# driver-phase.net
KiCad netlist of a schematic drawn in Altium Designer
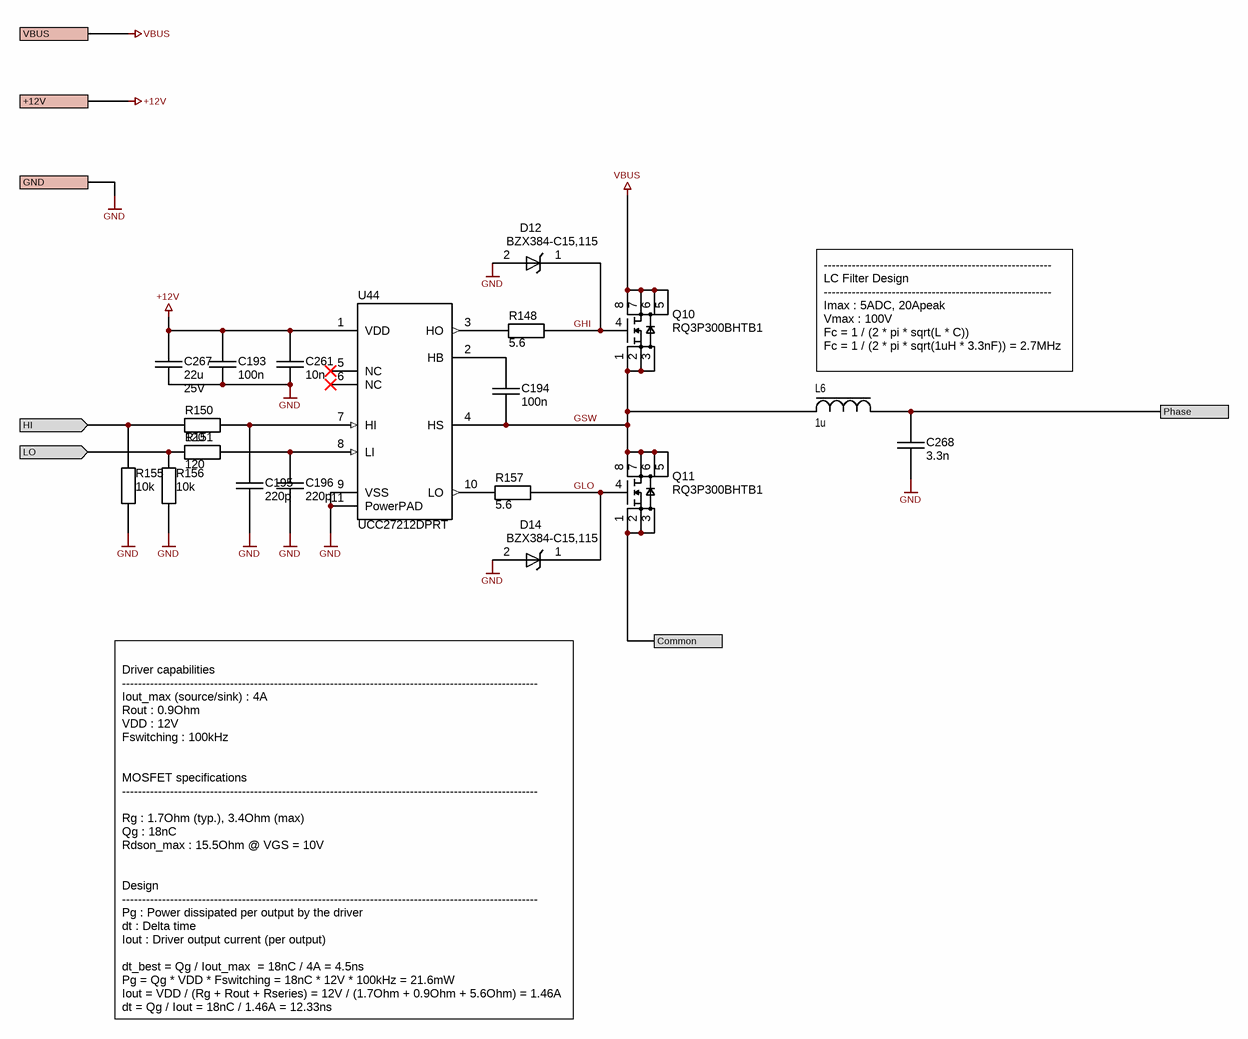
[diagram p0: driver-phase.SchDoc]

(export (version "E")
  (design (tool "Eeschema 10.0.6"))
  (components
    (comp (ref "C193")
      (value "100n")
      (footprint "SM/C0402")
      (description "100 nF ±10% 25V Ceramic Capacitor X5R 0402 (1005 Metric)")
      (fields (field (name "VOLTAGE") "25V"))
      (libsource (lib "motionboard") (part "CAP CER 100NF 25V X5R 0402"))
    )
    (comp (ref "C194")
      (value "100n")
      (footprint "SM/C0402")
      (description "100 nF ±10% 25V Ceramic Capacitor X5R 0402 (1005 Metric)")
      (fields (field (name "VOLTAGE") "25V"))
      (libsource (lib "motionboard") (part "CAP CER 100NF 25V X5R 0402"))
    )
    (comp (ref "C195")
      (value "220p")
      (footprint "SM/C0402")
      (description "220 pF ±5% 50V Ceramic Capacitor C0G, NP0 0402 (1005 Metric)")
      (fields (field (name "VOLTAGE") "50V"))
      (libsource (lib "motionboard") (part "CAP CER 220PF 50V C0G/NP0 0402"))
    )
    (comp (ref "C196")
      (value "220p")
      (footprint "SM/C0402")
      (description "220 pF ±5% 50V Ceramic Capacitor C0G, NP0 0402 (1005 Metric)")
      (fields (field (name "VOLTAGE") "50V"))
      (libsource (lib "motionboard") (part "CAP CER 220PF 50V C0G/NP0 0402"))
    )
    (comp (ref "C261")
      (value "10n")
      (footprint "SM/C0402")
      (description "10 nF ±10% 50V Ceramic Capacitor X7R 0402 (1005 Metric)")
      (fields (field (name "VOLTAGE") "50V"))
      (libsource (lib "motionboard") (part "CAP CER 10NF 50V X7R 0402"))
    )
    (comp (ref "C267")
      (value "22u")
      (footprint "SM/C0805")
      (description "22 µF ±20% 25V Ceramic Capacitor X5R 0805 (2012 Metric)")
      (fields (field (name "VOLTAGE") "25V"))
      (libsource (lib "motionboard") (part "CAP CER 22UF 25V X5R 0805"))
    )
    (comp (ref "C268")
      (value "3.3n")
      (footprint "SM/C0402")
      (description "3.3 nF ±10% 100V Ceramic Capacitor X8R 0402 (1005 Metric)")
      (fields (field (name "VOLTAGE") "16V"))
      (libsource (lib "motionboard") (part "CAP CER 3.3NF 100V X8R 0402"))
    )
    (comp (ref "D12")
      (value "BZX384-C15,115")
      (footprint "SODFL250X110-2N")
      (description "Zener Diode 15 V 300 mW ±5% Surface Mount SOD-323")
      (libsource (lib "motionboard") (part "DIODE ZENER 15V 300MW SOD323"))
    )
    (comp (ref "D14")
      (value "BZX384-C15,115")
      (footprint "SODFL250X110-2N")
      (description "Zener Diode 15 V 300 mW ±5% Surface Mount SOD-323")
      (libsource (lib "motionboard") (part "DIODE ZENER 15V 300MW SOD323"))
    )
    (comp (ref "L6")
      (value "1u")
      (footprint "PA5005.102NLT")
      (description "1 µH Shielded Molded Inductor 20 A 4.52mOhm Max Nonstandard")
      (libsource (lib "motionboard") (part "PA5005.102NLT"))
    )
    (comp (ref "Q10")
      (value "RQ3P300BHTB1")
      (footprint "RQ3P300BHTB1")
      (description "N-Channel 100 V 39A (Ta) 2W (Ta) Surface Mount 8-HSMT (3.2x3)")
      (libsource (lib "motionboard") (part "RQ3P300BHTB1"))
    )
    (comp (ref "Q11")
      (value "RQ3P300BHTB1")
      (footprint "RQ3P300BHTB1")
      (description "N-Channel 100 V 39A (Ta) 2W (Ta) Surface Mount 8-HSMT (3.2x3)")
      (libsource (lib "motionboard") (part "RQ3P300BHTB1"))
    )
    (comp (ref "R148")
      (value "5.6")
      (footprint "SM/R0402")
      (description "5.6 Ohms ±5% 0.063W, 1/16W Chip Resistor 0402 (1005 Metric) Moisture Resistant Thick Film")
      (libsource (lib "motionboard") (part "RES 5.6 OHM 5% 1/16W 0402"))
    )
    (comp (ref "R150")
      (value "120")
      (footprint "SM/R0402")
      (description "120 Ohms ±1% 0.063W, 1/16W Chip Resistor 0402 (1005 Metric) Moisture Resistant Thick Film")
      (libsource (lib "motionboard") (part "RES 120 OHM 1% 1/16W 0402"))
    )
    (comp (ref "R151")
      (value "120")
      (footprint "SM/R0402")
      (description "120 Ohms ±1% 0.063W, 1/16W Chip Resistor 0402 (1005 Metric) Moisture Resistant Thick Film")
      (libsource (lib "motionboard") (part "RES 120 OHM 1% 1/16W 0402"))
    )
    (comp (ref "R155")
      (value "10k")
      (footprint "SM/R0402")
      (description "10 kOhms ±1% 0.063W, 1/16W Chip Resistor 0402 (1005 Metric) Moisture Resistant Thick Film")
      (libsource (lib "motionboard") (part "RES 10K OHM 1% 1/16W 0402"))
    )
    (comp (ref "R156")
      (value "10k")
      (footprint "SM/R0402")
      (description "10 kOhms ±1% 0.063W, 1/16W Chip Resistor 0402 (1005 Metric) Moisture Resistant Thick Film")
      (libsource (lib "motionboard") (part "RES 10K OHM 1% 1/16W 0402"))
    )
    (comp (ref "R157")
      (value "5.6")
      (footprint "SM/R0402")
      (description "5.6 Ohms ±5% 0.063W, 1/16W Chip Resistor 0402 (1005 Metric) Moisture Resistant Thick Film")
      (libsource (lib "") (part "RES 5.6 OHM 5% 1/16W 0402_1"))
    )
    (comp (ref "U44")
      (value "UCC27212DPRT")
      (footprint "PSON80P400X80_HS-11N")
      (description "Half-Bridge Gate Driver IC Non-Inverting 10-WSON (4x4)")
      (libsource (lib "motionboard") (part "UCC27212"))
    )
  )
  (nets
    (net (code "1") (name "+12V") (class "Default")
      (node (ref "C193") (pin "2") (pintype "passive"))
      (node (ref "C261") (pin "1") (pintype "passive"))
      (node (ref "C267") (pin "2") (pintype "passive"))
      (node (ref "U44") (pin "1") (pinfunction "VDD_1") (pintype "power_in"))
    )
    (net (code "2") (name "/Common") (class "Default")
      (node (ref "Q11") (pin "1") (pinfunction "S_1") (pintype "passive"))
      (node (ref "Q11") (pin "2") (pinfunction "S_2") (pintype "passive"))
      (node (ref "Q11") (pin "3") (pinfunction "S_3") (pintype "passive"))
    )
    (net (code "3") (name "/GHI") (class "Default")
      (node (ref "D12") (pin "1") (pinfunction "K_1") (pintype "passive"))
      (node (ref "Q10") (pin "4") (pinfunction "G_4") (pintype "passive"))
      (node (ref "R148") (pin "2") (pintype "passive"))
    )
    (net (code "4") (name "/GLO") (class "Default")
      (node (ref "D14") (pin "1") (pinfunction "K_1") (pintype "passive"))
      (node (ref "Q11") (pin "4") (pinfunction "G_4") (pintype "passive"))
      (node (ref "R157") (pin "1") (pintype "passive"))
    )
    (net (code "5") (name "/GSW") (class "Default")
      (node (ref "C194") (pin "2") (pintype "passive"))
      (node (ref "L6") (pin "1") (pintype "passive"))
      (node (ref "Q10") (pin "1") (pinfunction "S_1") (pintype "passive"))
      (node (ref "Q10") (pin "2") (pinfunction "S_2") (pintype "passive"))
      (node (ref "Q10") (pin "3") (pinfunction "S_3") (pintype "passive"))
      (node (ref "Q11") (pin "5") (pinfunction "D_5") (pintype "passive"))
      (node (ref "Q11") (pin "6") (pinfunction "D_6") (pintype "passive"))
      (node (ref "Q11") (pin "7") (pinfunction "D_7") (pintype "passive"))
      (node (ref "Q11") (pin "8") (pinfunction "D_8") (pintype "passive"))
      (node (ref "U44") (pin "4") (pinfunction "HS_4") (pintype "power_in"))
    )
    (net (code "6") (name "/HI") (class "Default")
      (node (ref "R150") (pin "2") (pintype "passive"))
      (node (ref "R155") (pin "1") (pintype "passive"))
    )
    (net (code "7") (name "/LO") (class "Default")
      (node (ref "R151") (pin "2") (pintype "passive"))
      (node (ref "R156") (pin "1") (pintype "passive"))
    )
    (net (code "8") (name "/Phase") (class "Default")
      (node (ref "C268") (pin "2") (pintype "passive"))
      (node (ref "L6") (pin "2") (pintype "passive"))
    )
    (net (code "9") (name "GND") (class "Default")
      (node (ref "C193") (pin "1") (pintype "passive"))
      (node (ref "C195") (pin "1") (pintype "passive"))
      (node (ref "C196") (pin "1") (pintype "passive"))
      (node (ref "C261") (pin "2") (pintype "passive"))
      (node (ref "C267") (pin "1") (pintype "passive"))
      (node (ref "C268") (pin "1") (pintype "passive"))
      (node (ref "D12") (pin "2") (pinfunction "A_2") (pintype "power_in"))
      (node (ref "D14") (pin "2") (pinfunction "A_2") (pintype "power_in"))
      (node (ref "R155") (pin "2") (pintype "passive"))
      (node (ref "R156") (pin "2") (pintype "passive"))
      (node (ref "U44") (pin "11") (pinfunction "PowerPAD_11") (pintype "power_in"))
      (node (ref "U44") (pin "9") (pinfunction "VSS_9") (pintype "power_in"))
    )
    (net (code "10") (name "Net-(U44-HB)") (class "Default")
      (node (ref "C194") (pin "1") (pintype "passive"))
      (node (ref "U44") (pin "2") (pinfunction "HB_2") (pintype "power_in"))
    )
    (net (code "11") (name "Net-(U44-HI)") (class "Default")
      (node (ref "C195") (pin "2") (pintype "passive"))
      (node (ref "R150") (pin "1") (pintype "passive"))
      (node (ref "U44") (pin "7") (pinfunction "HI_7") (pintype "input"))
    )
    (net (code "12") (name "Net-(U44-HO)") (class "Default")
      (node (ref "R148") (pin "1") (pintype "passive"))
      (node (ref "U44") (pin "3") (pinfunction "HO_3") (pintype "output"))
    )
    (net (code "13") (name "Net-(U44-LI)") (class "Default")
      (node (ref "C196") (pin "2") (pintype "passive"))
      (node (ref "R151") (pin "1") (pintype "passive"))
      (node (ref "U44") (pin "8") (pinfunction "LI_8") (pintype "input"))
    )
    (net (code "14") (name "Net-(U44-LO)") (class "Default")
      (node (ref "R157") (pin "2") (pintype "passive"))
      (node (ref "U44") (pin "10") (pinfunction "LO_10") (pintype "output"))
    )
    (net (code "15") (name "VBUS") (class "Default")
      (node (ref "Q10") (pin "5") (pinfunction "D_5") (pintype "passive"))
      (node (ref "Q10") (pin "6") (pinfunction "D_6") (pintype "passive"))
      (node (ref "Q10") (pin "7") (pinfunction "D_7") (pintype "passive"))
      (node (ref "Q10") (pin "8") (pinfunction "D_8") (pintype "passive"))
    )
    (net (code "16") (name "unconnected-(U44-NC-Pad5)") (class "Default")
      (node (ref "U44") (pin "5") (pinfunction "NC_5") (pintype "passive+no_connect"))
    )
    (net (code "17") (name "unconnected-(U44-NC-Pad6)") (class "Default")
      (node (ref "U44") (pin "6") (pinfunction "NC_6") (pintype "passive+no_connect"))
    )
  )
)
